# SPin.net
KiCad netlist of a schematic drawn in EAGLE
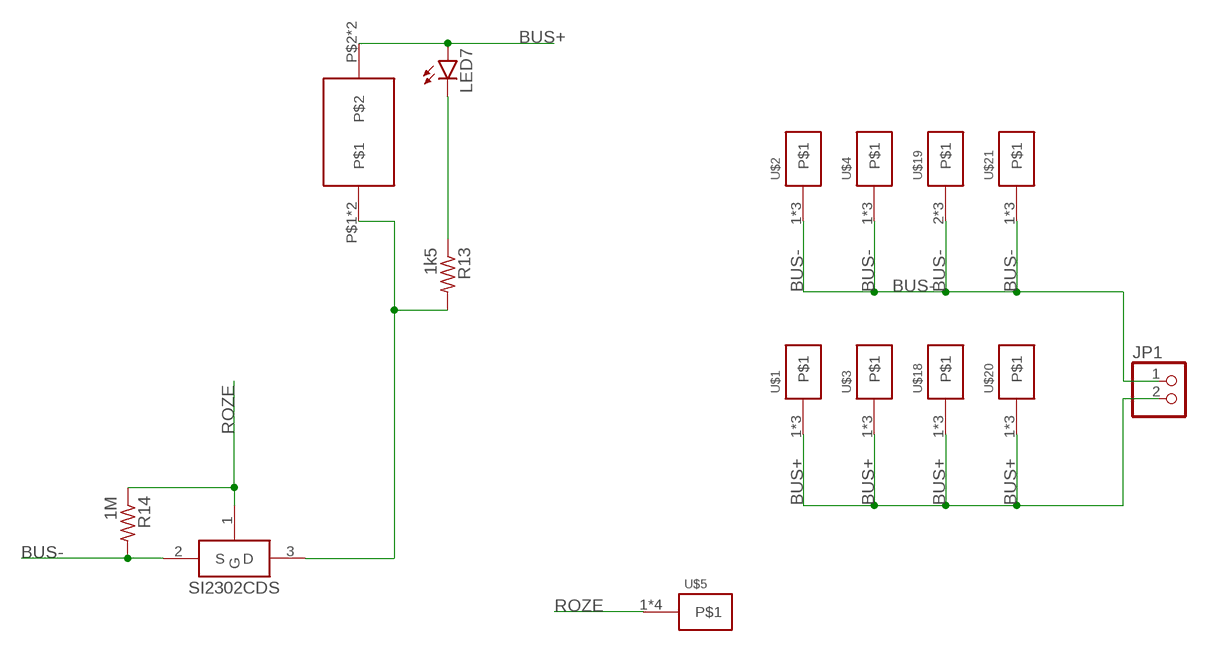
[diagram p0: schematic, sheet 1]

(export (version "E")
  (design (tool "Eeschema 10.0.6"))
  (components
    (comp (ref "JP1")
      (value "PINHD-1X2")
      (footprint "eagle-import:1X02")
      (libsource (lib "eagle-import") (part "PINHD-1X2"))
    )
    (comp (ref "LED7")
      (value "LEDCHIPLED_0603")
      (footprint "eagle-import:CHIPLED_0603")
      (libsource (lib "eagle-import") (part "LEDCHIPLED_0603"))
    )
    (comp (ref "R13")
      (value "1k5")
      (footprint "eagle-import:R0603")
      (libsource (lib "eagle-import") (part "R-US_R0603"))
    )
    (comp (ref "R14")
      (value "1M")
      (footprint "eagle-import:R0603")
      (libsource (lib "eagle-import") (part "R-US_R0603"))
    )
    (comp (ref "U$1")
      (value "KCONNECT3")
      (footprint "eagle-import:KCONNECT-3")
      (libsource (lib "eagle-import") (part "KCONNECT3"))
    )
    (comp (ref "U$2")
      (value "KCONNECT3")
      (footprint "eagle-import:KCONNECT-3")
      (libsource (lib "eagle-import") (part "KCONNECT3"))
    )
    (comp (ref "U$3")
      (value "KCONNECT4")
      (footprint "eagle-import:KCONNECT-4")
      (libsource (lib "eagle-import") (part "KCONNECT4"))
    )
    (comp (ref "U$4")
      (value "KCONNECT4")
      (footprint "eagle-import:KCONNECT-4")
      (libsource (lib "eagle-import") (part "KCONNECT4"))
    )
    (comp (ref "U$5")
      (value "KCONNECTQUAD-")
      (footprint "eagle-import:KCONNECT-_QUAD")
      (libsource (lib "eagle-import") (part "KCONNECTQUAD-"))
    )
    (comp (ref "U$6")
      (value "GRAFITGRAFIT4_2")
      (footprint "eagle-import:GRAFIT4_2")
      (libsource (lib "eagle-import") (part "GRAFITGRAFIT4_2"))
    )
    (comp (ref "U$13")
      (value "SI2302CDS")
      (footprint "eagle-import:SOT23-3")
      (libsource (lib "eagle-import") (part "SI2302CDS"))
    )
    (comp (ref "U$18")
      (value "KCONNECT4")
      (footprint "eagle-import:KCONNECT-4")
      (libsource (lib "eagle-import") (part "KCONNECT4"))
    )
    (comp (ref "U$19")
      (value "KCONNECT1")
      (footprint "eagle-import:KCONNECT-1")
      (libsource (lib "eagle-import") (part "KCONNECT1"))
    )
    (comp (ref "U$20")
      (value "KCONNECT3")
      (footprint "eagle-import:KCONNECT-3")
      (libsource (lib "eagle-import") (part "KCONNECT3"))
    )
    (comp (ref "U$21")
      (value "KCONNECT3")
      (footprint "eagle-import:KCONNECT-3")
      (libsource (lib "eagle-import") (part "KCONNECT3"))
    )
  )
  (nets
    (net (code "1") (name "/BUS+") (class "Default")
      (node (ref "JP1") (pin "2") (pinfunction "2_2") (pintype "passive"))
      (node (ref "LED7") (pin "A") (pinfunction "A_A") (pintype "passive"))
      (node (ref "U$1") (pin "1") (pinfunction "P$1_1") (pintype "bidirectional"))
      (node (ref "U$1") (pin "2") (pinfunction "P$1_2") (pintype "bidirectional"))
      (node (ref "U$1") (pin "4") (pinfunction "P$1_4") (pintype "bidirectional"))
      (node (ref "U$18") (pin "1") (pinfunction "P$1_1") (pintype "bidirectional"))
      (node (ref "U$18") (pin "2") (pinfunction "P$1_2") (pintype "bidirectional"))
      (node (ref "U$18") (pin "3") (pinfunction "P$1_3") (pintype "bidirectional"))
      (node (ref "U$20") (pin "1") (pinfunction "P$1_1") (pintype "bidirectional"))
      (node (ref "U$20") (pin "2") (pinfunction "P$1_2") (pintype "bidirectional"))
      (node (ref "U$20") (pin "4") (pinfunction "P$1_4") (pintype "bidirectional"))
      (node (ref "U$3") (pin "1") (pinfunction "P$1_1") (pintype "bidirectional"))
      (node (ref "U$3") (pin "2") (pinfunction "P$1_2") (pintype "bidirectional"))
      (node (ref "U$3") (pin "3") (pinfunction "P$1_3") (pintype "bidirectional"))
      (node (ref "U$6") (pin "P$2") (pinfunction "P$2_P$2") (pintype "bidirectional"))
      (node (ref "U$6") (pin "P$5") (pinfunction "P$2_P$5") (pintype "bidirectional"))
    )
    (net (code "2") (name "/BUS-") (class "Default")
      (node (ref "JP1") (pin "1") (pinfunction "1_1") (pintype "passive"))
      (node (ref "R14") (pin "2") (pinfunction "2_2") (pintype "passive"))
      (node (ref "U$13") (pin "2") (pinfunction "S_2") (pintype "bidirectional"))
      (node (ref "U$19") (pin "2") (pinfunction "P$1_2") (pintype "bidirectional"))
      (node (ref "U$19") (pin "3") (pinfunction "P$1_3") (pintype "bidirectional"))
      (node (ref "U$19") (pin "4") (pinfunction "P$1_4") (pintype "bidirectional"))
      (node (ref "U$2") (pin "1") (pinfunction "P$1_1") (pintype "bidirectional"))
      (node (ref "U$2") (pin "2") (pinfunction "P$1_2") (pintype "bidirectional"))
      (node (ref "U$2") (pin "4") (pinfunction "P$1_4") (pintype "bidirectional"))
      (node (ref "U$21") (pin "1") (pinfunction "P$1_1") (pintype "bidirectional"))
      (node (ref "U$21") (pin "2") (pinfunction "P$1_2") (pintype "bidirectional"))
      (node (ref "U$21") (pin "4") (pinfunction "P$1_4") (pintype "bidirectional"))
      (node (ref "U$4") (pin "1") (pinfunction "P$1_1") (pintype "bidirectional"))
      (node (ref "U$4") (pin "2") (pinfunction "P$1_2") (pintype "bidirectional"))
      (node (ref "U$4") (pin "3") (pinfunction "P$1_3") (pintype "bidirectional"))
    )
    (net (code "3") (name "/ROZE") (class "Default")
      (node (ref "R14") (pin "1") (pinfunction "1_1") (pintype "passive"))
      (node (ref "U$13") (pin "1") (pinfunction "G_1") (pintype "bidirectional"))
      (node (ref "U$5") (pin "1") (pinfunction "P$1_1") (pintype "bidirectional"))
      (node (ref "U$5") (pin "2") (pinfunction "P$1_2") (pintype "bidirectional"))
      (node (ref "U$5") (pin "3") (pinfunction "P$1_3") (pintype "bidirectional"))
      (node (ref "U$5") (pin "4") (pinfunction "P$1_4") (pintype "bidirectional"))
    )
    (net (code "4") (name "Net-(LED7-PadC)") (class "Default")
      (node (ref "LED7") (pin "C") (pinfunction "C_C") (pintype "passive"))
      (node (ref "R13") (pin "1") (pinfunction "1_1") (pintype "passive"))
    )
    (net (code "5") (name "Net-(U$13-D)") (class "Default")
      (node (ref "R13") (pin "2") (pinfunction "2_2") (pintype "passive"))
      (node (ref "U$13") (pin "3") (pinfunction "D_3") (pintype "bidirectional"))
      (node (ref "U$6") (pin "P$1") (pinfunction "P$1_P$1") (pintype "bidirectional"))
      (node (ref "U$6") (pin "P$4") (pinfunction "P$1_P$4") (pintype "bidirectional"))
    )
  )
)
